# SoM-LowSpeed.net
KiCad netlist of a schematic drawn in Altium Designer
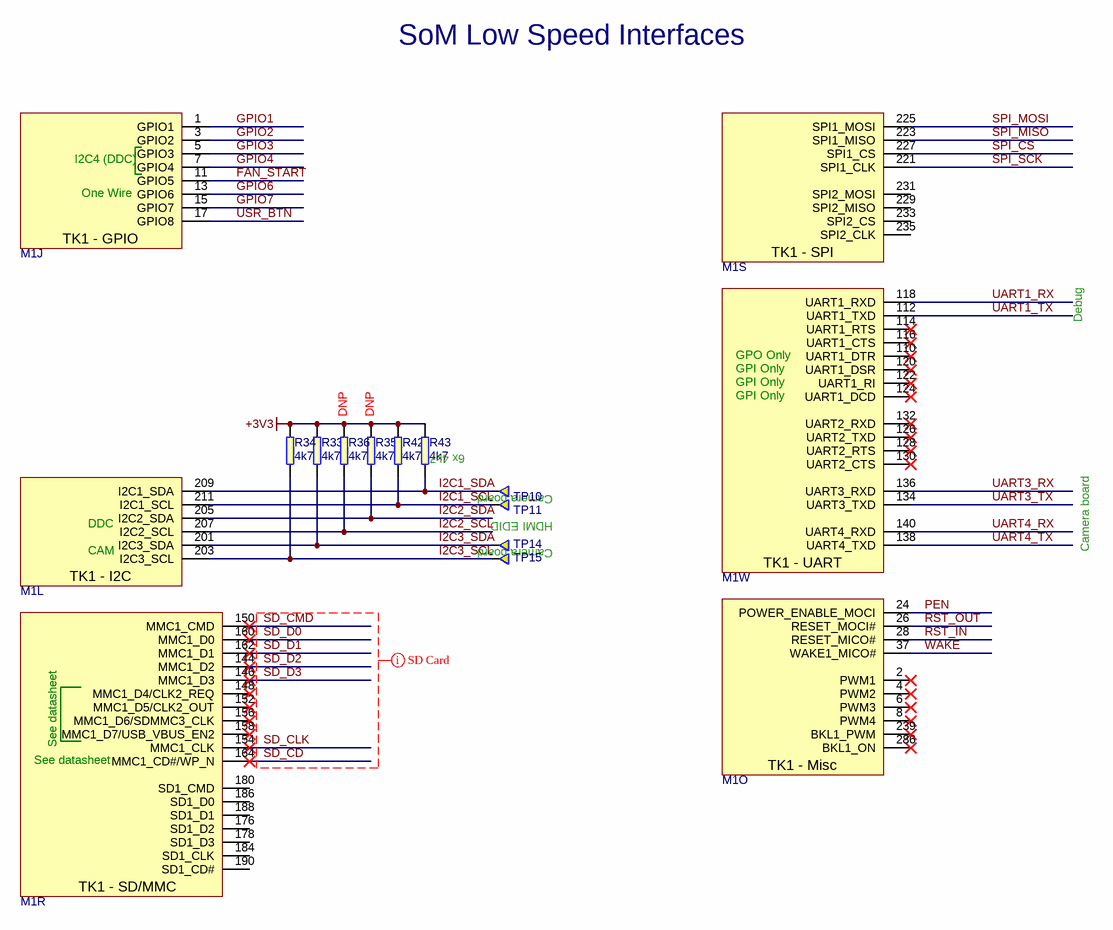
[diagram p0: SoM-LowSpeed.SchDoc]

(export (version "E")
  (design (tool "Eeschema 10.0.6"))
  (components
    (comp (ref "M1")
      (value "MM70-314-310B1")
      (footprint "Apalis-H")
      (description "Toradex Apalis TK1, Horizontal")
      (fields (field (name "PART NUMBER") "Apalis-TK1-H") (field (name "MANUFACTURER") "JAE Electronics"))
      (libsource (lib "TK1Baseboard") (part "Apalis-TK1-H"))
    )
    (comp (ref "R33")
      (value "4k7")
      (footprint "0402")
      (description "RES, 4k7, 0402")
      (fields (field (name "MANUFACTURER") "Panasonic") (field (name "PART NUMBER") "R_4k7_0402"))
      (libsource (lib "TK1Baseboard") (part "R_4k7_0402"))
    )
    (comp (ref "R34")
      (value "4k7")
      (footprint "0402")
      (description "RES, 4k7, 0402")
      (fields (field (name "MANUFACTURER") "Panasonic") (field (name "PART NUMBER") "R_4k7_0402"))
      (libsource (lib "TK1Baseboard") (part "R_4k7_0402"))
    )
    (comp (ref "R35")
      (value "4k7")
      (footprint "0402")
      (description "RES, 4k7, 0402")
      (fields (field (name "MANUFACTURER") "Panasonic") (field (name "PART NUMBER") "R_4k7_0402"))
      (libsource (lib "TK1Baseboard") (part "R_4k7_0402"))
    )
    (comp (ref "R36")
      (value "4k7")
      (footprint "0402")
      (description "RES, 4k7, 0402")
      (fields (field (name "MANUFACTURER") "Panasonic") (field (name "PART NUMBER") "R_4k7_0402"))
      (libsource (lib "TK1Baseboard") (part "R_4k7_0402"))
    )
    (comp (ref "R42")
      (value "4k7")
      (footprint "0402")
      (description "RES, 4k7, 0402")
      (fields (field (name "MANUFACTURER") "Panasonic") (field (name "PART NUMBER") "R_4k7_0402"))
      (libsource (lib "TK1Baseboard") (part "R_4k7_0402"))
    )
    (comp (ref "R43")
      (value "4k7")
      (footprint "0402")
      (description "RES, 4k7, 0402")
      (fields (field (name "MANUFACTURER") "Panasonic") (field (name "PART NUMBER") "R_4k7_0402"))
      (libsource (lib "TK1Baseboard") (part "R_4k7_0402"))
    )
    (comp (ref "TP10")
      (value "TP-R-1.5")
      (footprint "TP-R-1.5")
      (description "Testpad, round, 1.5mm")
      (libsource (lib "TK1Baseboard") (part "TP-R-1.5"))
    )
    (comp (ref "TP11")
      (value "TP-R-1.5")
      (footprint "TP-R-1.5")
      (description "Testpad, round, 1.5mm")
      (libsource (lib "TK1Baseboard") (part "TP-R-1.5"))
    )
    (comp (ref "TP14")
      (value "TP-R-1.5")
      (footprint "TP-R-1.5")
      (description "Testpad, round, 1.5mm")
      (libsource (lib "TK1Baseboard") (part "TP-R-1.5"))
    )
    (comp (ref "TP15")
      (value "TP-R-1.5")
      (footprint "TP-R-1.5")
      (description "Testpad, round, 1.5mm")
      (libsource (lib "TK1Baseboard") (part "TP-R-1.5"))
    )
  )
  (nets
    (net (code "1") (name "+3V3") (class "Default")
      (node (ref "R33") (pin "2") (pintype "passive"))
      (node (ref "R34") (pin "2") (pintype "passive"))
      (node (ref "R35") (pin "2") (pintype "passive"))
      (node (ref "R36") (pin "2") (pintype "passive"))
      (node (ref "R42") (pin "2") (pintype "passive"))
      (node (ref "R43") (pin "2") (pintype "passive"))
    )
    (net (code "2") (name "/FAN_START") (class "Default")
      (node (ref "M1") (pin "11") (pinfunction "GPIO5_11") (pintype "passive"))
    )
    (net (code "3") (name "/GPIO1") (class "Default")
      (node (ref "M1") (pin "1") (pinfunction "GPIO1_1") (pintype "passive"))
    )
    (net (code "4") (name "/GPIO2") (class "Default")
      (node (ref "M1") (pin "3") (pinfunction "GPIO2_3") (pintype "passive"))
    )
    (net (code "5") (name "/GPIO3") (class "Default")
      (node (ref "M1") (pin "5") (pinfunction "GPIO3_5") (pintype "passive"))
    )
    (net (code "6") (name "/GPIO4") (class "Default")
      (node (ref "M1") (pin "7") (pinfunction "GPIO4_7") (pintype "passive"))
    )
    (net (code "7") (name "/GPIO6") (class "Default")
      (node (ref "M1") (pin "13") (pinfunction "GPIO6_13") (pintype "passive"))
    )
    (net (code "8") (name "/GPIO7") (class "Default")
      (node (ref "M1") (pin "15") (pinfunction "GPIO7_15") (pintype "passive"))
    )
    (net (code "9") (name "/I2C1_SCL") (class "Default")
      (node (ref "M1") (pin "211") (pinfunction "I2C1_SCL_211") (pintype "passive"))
      (node (ref "R42") (pin "1") (pintype "passive"))
      (node (ref "TP11") (pin "1") (pintype "passive"))
    )
    (net (code "10") (name "/I2C1_SDA") (class "Default")
      (node (ref "M1") (pin "209") (pinfunction "I2C1_SDA_209") (pintype "passive"))
      (node (ref "R43") (pin "1") (pintype "passive"))
      (node (ref "TP10") (pin "1") (pintype "passive"))
    )
    (net (code "11") (name "/I2C2_SCL") (class "Default")
      (node (ref "M1") (pin "207") (pinfunction "I2C2_SCL_207") (pintype "passive"))
      (node (ref "R36") (pin "1") (pintype "passive"))
    )
    (net (code "12") (name "/I2C2_SDA") (class "Default")
      (node (ref "M1") (pin "205") (pinfunction "I2C2_SDA_205") (pintype "passive"))
      (node (ref "R35") (pin "1") (pintype "passive"))
    )
    (net (code "13") (name "/I2C3_SCL") (class "Default")
      (node (ref "M1") (pin "203") (pinfunction "I2C3_SCL_203") (pintype "passive"))
      (node (ref "R34") (pin "1") (pintype "passive"))
      (node (ref "TP15") (pin "1") (pintype "passive"))
    )
    (net (code "14") (name "/I2C3_SDA") (class "Default")
      (node (ref "M1") (pin "201") (pinfunction "I2C3_SDA_201") (pintype "passive"))
      (node (ref "R33") (pin "1") (pintype "passive"))
      (node (ref "TP14") (pin "1") (pintype "passive"))
    )
    (net (code "15") (name "/PEN") (class "Default")
      (node (ref "M1") (pin "24") (pinfunction "POWER_ENABLE_MOCI_24") (pintype "passive"))
    )
    (net (code "16") (name "/RST_IN") (class "Default")
      (node (ref "M1") (pin "28") (pinfunction "RESET_MICO#_28") (pintype "passive"))
    )
    (net (code "17") (name "/RST_OUT") (class "Default")
      (node (ref "M1") (pin "26") (pinfunction "RESET_MOCI#_26") (pintype "passive"))
    )
    (net (code "18") (name "/SD_CD") (class "Default")
      (node (ref "M1") (pin "164") (pinfunction "MMC1_CD#/WP_N_164") (pintype "passive+no_connect"))
    )
    (net (code "19") (name "/SD_CLK") (class "Default")
      (node (ref "M1") (pin "154") (pinfunction "MMC1_CLK_154") (pintype "passive+no_connect"))
    )
    (net (code "20") (name "/SD_CMD") (class "Default")
      (node (ref "M1") (pin "150") (pinfunction "MMC1_CMD_150") (pintype "passive+no_connect"))
    )
    (net (code "21") (name "/SD_D0") (class "Default")
      (node (ref "M1") (pin "160") (pinfunction "MMC1_D0_160") (pintype "passive+no_connect"))
    )
    (net (code "22") (name "/SD_D1") (class "Default")
      (node (ref "M1") (pin "162") (pinfunction "MMC1_D1_162") (pintype "passive+no_connect"))
    )
    (net (code "23") (name "/SD_D2") (class "Default")
      (node (ref "M1") (pin "144") (pinfunction "MMC1_D2_144") (pintype "passive+no_connect"))
    )
    (net (code "24") (name "/SD_D3") (class "Default")
      (node (ref "M1") (pin "146") (pinfunction "MMC1_D3_146") (pintype "passive+no_connect"))
    )
    (net (code "25") (name "/SPI_CS") (class "Default")
      (node (ref "M1") (pin "227") (pinfunction "SPI1_CS_227") (pintype "passive"))
    )
    (net (code "26") (name "/SPI_MISO") (class "Default")
      (node (ref "M1") (pin "223") (pinfunction "SPI1_MISO_223") (pintype "passive"))
    )
    (net (code "27") (name "/SPI_MOSI") (class "Default")
      (node (ref "M1") (pin "225") (pinfunction "SPI1_MOSI_225") (pintype "passive"))
    )
    (net (code "28") (name "/SPI_SCK") (class "Default")
      (node (ref "M1") (pin "221") (pinfunction "SPI1_CLK_221") (pintype "passive"))
    )
    (net (code "29") (name "/UART1_RX") (class "Default")
      (node (ref "M1") (pin "118") (pinfunction "UART1_RXD_118") (pintype "passive"))
    )
    (net (code "30") (name "/UART1_TX") (class "Default")
      (node (ref "M1") (pin "112") (pinfunction "UART1_TXD_112") (pintype "passive"))
    )
    (net (code "31") (name "/UART3_RX") (class "Default")
      (node (ref "M1") (pin "136") (pinfunction "UART3_RXD_136") (pintype "passive"))
    )
    (net (code "32") (name "/UART3_TX") (class "Default")
      (node (ref "M1") (pin "134") (pinfunction "UART3_TXD_134") (pintype "passive"))
    )
    (net (code "33") (name "/UART4_RX") (class "Default")
      (node (ref "M1") (pin "140") (pinfunction "UART4_RXD_140") (pintype "passive"))
    )
    (net (code "34") (name "/UART4_TX") (class "Default")
      (node (ref "M1") (pin "138") (pinfunction "UART4_TXD_138") (pintype "passive"))
    )
    (net (code "35") (name "/USR_BTN") (class "Default")
      (node (ref "M1") (pin "17") (pinfunction "GPIO8_17") (pintype "passive"))
    )
    (net (code "36") (name "/WAKE") (class "Default")
      (node (ref "M1") (pin "37") (pinfunction "WAKE1_MICO#_37") (pintype "passive"))
    )
    (net (code "37") (name "unconnected-(M1O-BKL1_ON-Pad286)") (class "Default")
      (node (ref "M1") (pin "286") (pinfunction "BKL1_ON_286") (pintype "passive+no_connect"))
    )
    (net (code "38") (name "unconnected-(M1O-BKL1_PWM-Pad239)") (class "Default")
      (node (ref "M1") (pin "239") (pinfunction "BKL1_PWM_239") (pintype "passive+no_connect"))
    )
    (net (code "39") (name "unconnected-(M1O-PWM1-Pad2)") (class "Default")
      (node (ref "M1") (pin "2") (pinfunction "PWM1_2") (pintype "passive+no_connect"))
    )
    (net (code "40") (name "unconnected-(M1O-PWM2-Pad4)") (class "Default")
      (node (ref "M1") (pin "4") (pinfunction "PWM2_4") (pintype "passive+no_connect"))
    )
    (net (code "41") (name "unconnected-(M1O-PWM3-Pad6)") (class "Default")
      (node (ref "M1") (pin "6") (pinfunction "PWM3_6") (pintype "passive+no_connect"))
    )
    (net (code "42") (name "unconnected-(M1O-PWM4-Pad8)") (class "Default")
      (node (ref "M1") (pin "8") (pinfunction "PWM4_8") (pintype "passive+no_connect"))
    )
    (net (code "43") (name "unconnected-(M1R-MMC1_D4{slash}CLK2_REQ-Pad148)") (class "Default")
      (node (ref "M1") (pin "148") (pinfunction "MMC1_D4/CLK2_REQ_148") (pintype "passive+no_connect"))
    )
    (net (code "44") (name "unconnected-(M1R-MMC1_D5{slash}CLK2_OUT-Pad152)") (class "Default")
      (node (ref "M1") (pin "152") (pinfunction "MMC1_D5/CLK2_OUT_152") (pintype "passive+no_connect"))
    )
    (net (code "45") (name "unconnected-(M1R-MMC1_D6{slash}SDMMC3_CLK-Pad156)") (class "Default")
      (node (ref "M1") (pin "156") (pinfunction "MMC1_D6/SDMMC3_CLK_156") (pintype "passive+no_connect"))
    )
    (net (code "46") (name "unconnected-(M1R-MMC1_D7{slash}USB_VBUS_EN2-Pad158)") (class "Default")
      (node (ref "M1") (pin "158") (pinfunction "MMC1_D7/USB_VBUS_EN2_158") (pintype "passive+no_connect"))
    )
    (net (code "47") (name "unconnected-(M1R-SD1_CD#-Pad190)") (class "Default")
      (node (ref "M1") (pin "190") (pinfunction "SD1_CD#_190") (pintype "passive"))
    )
    (net (code "48") (name "unconnected-(M1R-SD1_CLK-Pad184)") (class "Default")
      (node (ref "M1") (pin "184") (pinfunction "SD1_CLK_184") (pintype "passive"))
    )
    (net (code "49") (name "unconnected-(M1R-SD1_CMD-Pad180)") (class "Default")
      (node (ref "M1") (pin "180") (pinfunction "SD1_CMD_180") (pintype "passive"))
    )
    (net (code "50") (name "unconnected-(M1R-SD1_D0-Pad186)") (class "Default")
      (node (ref "M1") (pin "186") (pinfunction "SD1_D0_186") (pintype "passive"))
    )
    (net (code "51") (name "unconnected-(M1R-SD1_D1-Pad188)") (class "Default")
      (node (ref "M1") (pin "188") (pinfunction "SD1_D1_188") (pintype "passive"))
    )
    (net (code "52") (name "unconnected-(M1R-SD1_D2-Pad176)") (class "Default")
      (node (ref "M1") (pin "176") (pinfunction "SD1_D2_176") (pintype "passive"))
    )
    (net (code "53") (name "unconnected-(M1R-SD1_D3-Pad178)") (class "Default")
      (node (ref "M1") (pin "178") (pinfunction "SD1_D3_178") (pintype "passive"))
    )
    (net (code "54") (name "unconnected-(M1S-SPI2_CLK-Pad235)") (class "Default")
      (node (ref "M1") (pin "235") (pinfunction "SPI2_CLK_235") (pintype "passive"))
    )
    (net (code "55") (name "unconnected-(M1S-SPI2_CS-Pad233)") (class "Default")
      (node (ref "M1") (pin "233") (pinfunction "SPI2_CS_233") (pintype "passive"))
    )
    (net (code "56") (name "unconnected-(M1S-SPI2_MISO-Pad229)") (class "Default")
      (node (ref "M1") (pin "229") (pinfunction "SPI2_MISO_229") (pintype "passive"))
    )
    (net (code "57") (name "unconnected-(M1S-SPI2_MOSI-Pad231)") (class "Default")
      (node (ref "M1") (pin "231") (pinfunction "SPI2_MOSI_231") (pintype "passive"))
    )
    (net (code "58") (name "unconnected-(M1W-UART1_CTS-Pad116)") (class "Default")
      (node (ref "M1") (pin "116") (pinfunction "UART1_CTS_116") (pintype "passive+no_connect"))
    )
    (net (code "59") (name "unconnected-(M1W-UART1_DCD-Pad124)") (class "Default")
      (node (ref "M1") (pin "124") (pinfunction "UART1_DCD_124") (pintype "passive+no_connect"))
    )
    (net (code "60") (name "unconnected-(M1W-UART1_DSR-Pad120)") (class "Default")
      (node (ref "M1") (pin "120") (pinfunction "UART1_DSR_120") (pintype "passive+no_connect"))
    )
    (net (code "61") (name "unconnected-(M1W-UART1_DTR-Pad110)") (class "Default")
      (node (ref "M1") (pin "110") (pinfunction "UART1_DTR_110") (pintype "passive+no_connect"))
    )
    (net (code "62") (name "unconnected-(M1W-UART1_RI-Pad122)") (class "Default")
      (node (ref "M1") (pin "122") (pinfunction "UART1_RI_122") (pintype "passive+no_connect"))
    )
    (net (code "63") (name "unconnected-(M1W-UART1_RTS-Pad114)") (class "Default")
      (node (ref "M1") (pin "114") (pinfunction "UART1_RTS_114") (pintype "passive+no_connect"))
    )
    (net (code "64") (name "unconnected-(M1W-UART2_CTS-Pad130)") (class "Default")
      (node (ref "M1") (pin "130") (pinfunction "UART2_CTS_130") (pintype "passive+no_connect"))
    )
    (net (code "65") (name "unconnected-(M1W-UART2_RTS-Pad128)") (class "Default")
      (node (ref "M1") (pin "128") (pinfunction "UART2_RTS_128") (pintype "passive+no_connect"))
    )
    (net (code "66") (name "unconnected-(M1W-UART2_RXD-Pad132)") (class "Default")
      (node (ref "M1") (pin "132") (pinfunction "UART2_RXD_132") (pintype "passive+no_connect"))
    )
    (net (code "67") (name "unconnected-(M1W-UART2_TXD-Pad126)") (class "Default")
      (node (ref "M1") (pin "126") (pinfunction "UART2_TXD_126") (pintype "passive+no_connect"))
    )
  )
)
